# Motor_driver.net
KiCad netlist of a schematic drawn in Altium Designer
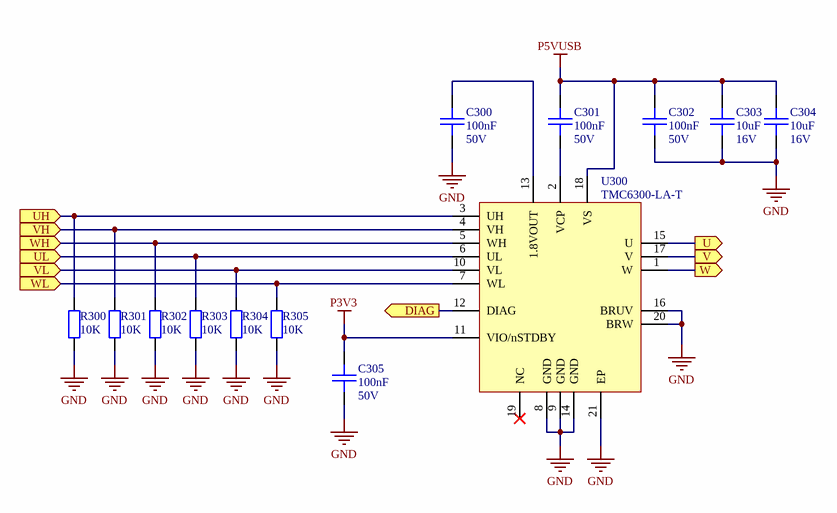
[diagram p0: Motor_driver.SchDoc]

(export (version "E")
  (design (tool "Eeschema 10.0.6"))
  (components
    (comp (ref "C300")
      (value "100nF")
      (footprint "C0402")
      (description "General purpose ceramic capacitor")
      (fields
        (field (name "VOLTAGE") "50V")
        (field (name "MANUFACTURER") "Murata Electronics")
        (field (name "MANUFACTURER PART NO") "GRT155R71H104KE01D")
      )
      (libsource (lib "Moonlight_Library") (part "CAP"))
    )
    (comp (ref "C301")
      (value "100nF")
      (footprint "C0402")
      (description "General purpose ceramic capacitor")
      (fields
        (field (name "VOLTAGE") "50V")
        (field (name "MANUFACTURER") "Murata Electronics")
        (field (name "MANUFACTURER PART NO") "GRT155R71H104KE01D")
      )
      (libsource (lib "Moonlight_Library") (part "CAP"))
    )
    (comp (ref "C302")
      (value "100nF")
      (footprint "C0402")
      (description "General purpose ceramic capacitor")
      (fields
        (field (name "VOLTAGE") "50V")
        (field (name "MANUFACTURER") "Murata Electronics")
        (field (name "MANUFACTURER PART NO") "GRT155R71H104KE01D")
      )
      (libsource (lib "Moonlight_Library") (part "CAP"))
    )
    (comp (ref "C303")
      (value "10uF")
      (footprint "C0805")
      (description "General purpose ceramic capacitor")
      (fields
        (field (name "VOLTAGE") "16V")
        (field (name "MANUFACTURER") "TDK Corporation")
        (field (name "MANUFACTURER PART NO") "CGA4J1X7S1C106K125AC")
      )
      (libsource (lib "Moonlight_Library") (part "CAP"))
    )
    (comp (ref "C304")
      (value "10uF")
      (footprint "C0805")
      (description "General purpose ceramic capacitor")
      (fields
        (field (name "VOLTAGE") "16V")
        (field (name "MANUFACTURER") "TDK Corporation")
        (field (name "MANUFACTURER PART NO") "CGA4J1X7S1C106K125AC")
      )
      (libsource (lib "Moonlight_Library") (part "CAP"))
    )
    (comp (ref "C305")
      (value "100nF")
      (footprint "C0402")
      (description "General purpose ceramic capacitor")
      (fields
        (field (name "VOLTAGE") "50V")
        (field (name "MANUFACTURER") "Murata Electronics")
        (field (name "MANUFACTURER PART NO") "GRT155R71H104KE01D")
      )
      (libsource (lib "Moonlight_Library") (part "CAP"))
    )
    (comp (ref "R300")
      (value "10K")
      (footprint "R0402")
      (description "General purpose resistor")
      (fields (field (name "MANUFACTURER PART NO") "Generic resistor") (field (name "Comment") "RES"))
      (libsource (lib "Moonlight_Library") (part "RES"))
    )
    (comp (ref "R301")
      (value "10K")
      (footprint "R0402")
      (description "General purpose resistor")
      (fields (field (name "MANUFACTURER PART NO") "Generic resistor") (field (name "Comment") "RES"))
      (libsource (lib "Moonlight_Library") (part "RES"))
    )
    (comp (ref "R302")
      (value "10K")
      (footprint "R0402")
      (description "General purpose resistor")
      (fields (field (name "MANUFACTURER PART NO") "Generic resistor") (field (name "Comment") "RES"))
      (libsource (lib "Moonlight_Library") (part "RES"))
    )
    (comp (ref "R303")
      (value "10K")
      (footprint "R0402")
      (description "General purpose resistor")
      (fields (field (name "MANUFACTURER PART NO") "Generic resistor") (field (name "Comment") "RES"))
      (libsource (lib "Moonlight_Library") (part "RES"))
    )
    (comp (ref "R304")
      (value "10K")
      (footprint "R0402")
      (description "General purpose resistor")
      (fields (field (name "MANUFACTURER PART NO") "Generic resistor") (field (name "Comment") "RES"))
      (libsource (lib "Moonlight_Library") (part "RES"))
    )
    (comp (ref "R305")
      (value "10K")
      (footprint "R0402")
      (description "General purpose resistor")
      (fields (field (name "MANUFACTURER PART NO") "Generic resistor") (field (name "Comment") "RES"))
      (libsource (lib "Moonlight_Library") (part "RES"))
    )
    (comp (ref "U300")
      (value "TMC6300")
      (footprint "TMC6300")
      (description "2-11V 2A 3-phase BLDC motor driver")
      (fields
        (field (name "MANUFACTURER") "Trinamic Motion Control GmbH")
        (field (name "MANUFACTURER PART NO") "TMC6300-LA-T")
      )
      (libsource (lib "Moonlight_Library") (part "TMC6300"))
    )
  )
  (nets
    (net (code "1") (name "/DIAG") (class "Default")
      (node (ref "U300") (pin "12") (pinfunction "DIAG_12") (pintype "passive"))
    )
    (net (code "2") (name "/U") (class "Default")
      (node (ref "U300") (pin "15") (pinfunction "U_15") (pintype "passive"))
    )
    (net (code "3") (name "/UH") (class "Default")
      (node (ref "R300") (pin "2") (pintype "passive"))
      (node (ref "U300") (pin "3") (pinfunction "UH_3") (pintype "passive"))
    )
    (net (code "4") (name "/UL") (class "Default")
      (node (ref "R303") (pin "2") (pintype "passive"))
      (node (ref "U300") (pin "6") (pinfunction "UL_6") (pintype "passive"))
    )
    (net (code "5") (name "/V") (class "Default")
      (node (ref "U300") (pin "17") (pinfunction "V_17") (pintype "passive"))
    )
    (net (code "6") (name "/VH") (class "Default")
      (node (ref "R301") (pin "2") (pintype "passive"))
      (node (ref "U300") (pin "4") (pinfunction "VH_4") (pintype "passive"))
    )
    (net (code "7") (name "/VL") (class "Default")
      (node (ref "R304") (pin "2") (pintype "passive"))
      (node (ref "U300") (pin "10") (pinfunction "VL_10") (pintype "passive"))
    )
    (net (code "8") (name "/W") (class "Default")
      (node (ref "U300") (pin "1") (pinfunction "W_1") (pintype "passive"))
    )
    (net (code "9") (name "/WH") (class "Default")
      (node (ref "R302") (pin "2") (pintype "passive"))
      (node (ref "U300") (pin "5") (pinfunction "WH_5") (pintype "passive"))
    )
    (net (code "10") (name "/WL") (class "Default")
      (node (ref "R305") (pin "2") (pintype "passive"))
      (node (ref "U300") (pin "7") (pinfunction "WL_7") (pintype "passive"))
    )
    (net (code "11") (name "GND") (class "Default")
      (node (ref "C300") (pin "2") (pinfunction "2_2") (pintype "passive"))
      (node (ref "C302") (pin "2") (pinfunction "2_2") (pintype "passive"))
      (node (ref "C303") (pin "2") (pinfunction "2_2") (pintype "passive"))
      (node (ref "C304") (pin "2") (pinfunction "2_2") (pintype "passive"))
      (node (ref "C305") (pin "2") (pinfunction "2_2") (pintype "passive"))
      (node (ref "R300") (pin "1") (pintype "passive"))
      (node (ref "R301") (pin "1") (pintype "passive"))
      (node (ref "R302") (pin "1") (pintype "passive"))
      (node (ref "R303") (pin "1") (pintype "passive"))
      (node (ref "R304") (pin "1") (pintype "passive"))
      (node (ref "R305") (pin "1") (pintype "passive"))
      (node (ref "U300") (pin "14") (pinfunction "GND_14") (pintype "passive"))
      (node (ref "U300") (pin "16") (pinfunction "BRUV_16") (pintype "passive"))
      (node (ref "U300") (pin "20") (pinfunction "BRW_20") (pintype "passive"))
      (node (ref "U300") (pin "21") (pinfunction "EP_21") (pintype "passive"))
      (node (ref "U300") (pin "8") (pinfunction "GND_8") (pintype "passive"))
      (node (ref "U300") (pin "9") (pinfunction "GND_9") (pintype "passive"))
    )
    (net (code "12") (name "Net-(U300-1.8VOUT)") (class "Default")
      (node (ref "C300") (pin "1") (pinfunction "1_1") (pintype "passive"))
      (node (ref "U300") (pin "13") (pinfunction "1.8VOUT_13") (pintype "passive"))
    )
    (net (code "13") (name "Net-(U300-VCP)") (class "Default")
      (node (ref "C301") (pin "2") (pinfunction "2_2") (pintype "passive"))
      (node (ref "U300") (pin "2") (pinfunction "VCP_2") (pintype "passive"))
    )
    (net (code "14") (name "P3V3") (class "Default")
      (node (ref "C305") (pin "1") (pinfunction "1_1") (pintype "passive"))
      (node (ref "U300") (pin "11") (pinfunction "VIO/nSTDBY_11") (pintype "passive"))
    )
    (net (code "15") (name "P5VUSB") (class "Default")
      (node (ref "C301") (pin "1") (pinfunction "1_1") (pintype "passive"))
      (node (ref "C302") (pin "1") (pinfunction "1_1") (pintype "passive"))
      (node (ref "C303") (pin "1") (pinfunction "1_1") (pintype "passive"))
      (node (ref "C304") (pin "1") (pinfunction "1_1") (pintype "passive"))
      (node (ref "U300") (pin "18") (pinfunction "VS_18") (pintype "passive"))
    )
    (net (code "16") (name "unconnected-(U300-NC-Pad19)") (class "Default")
      (node (ref "U300") (pin "19") (pinfunction "NC_19") (pintype "passive+no_connect"))
    )
  )
)
